# Qwiic_LED_Stick.net
KiCad netlist of a schematic drawn in EAGLE
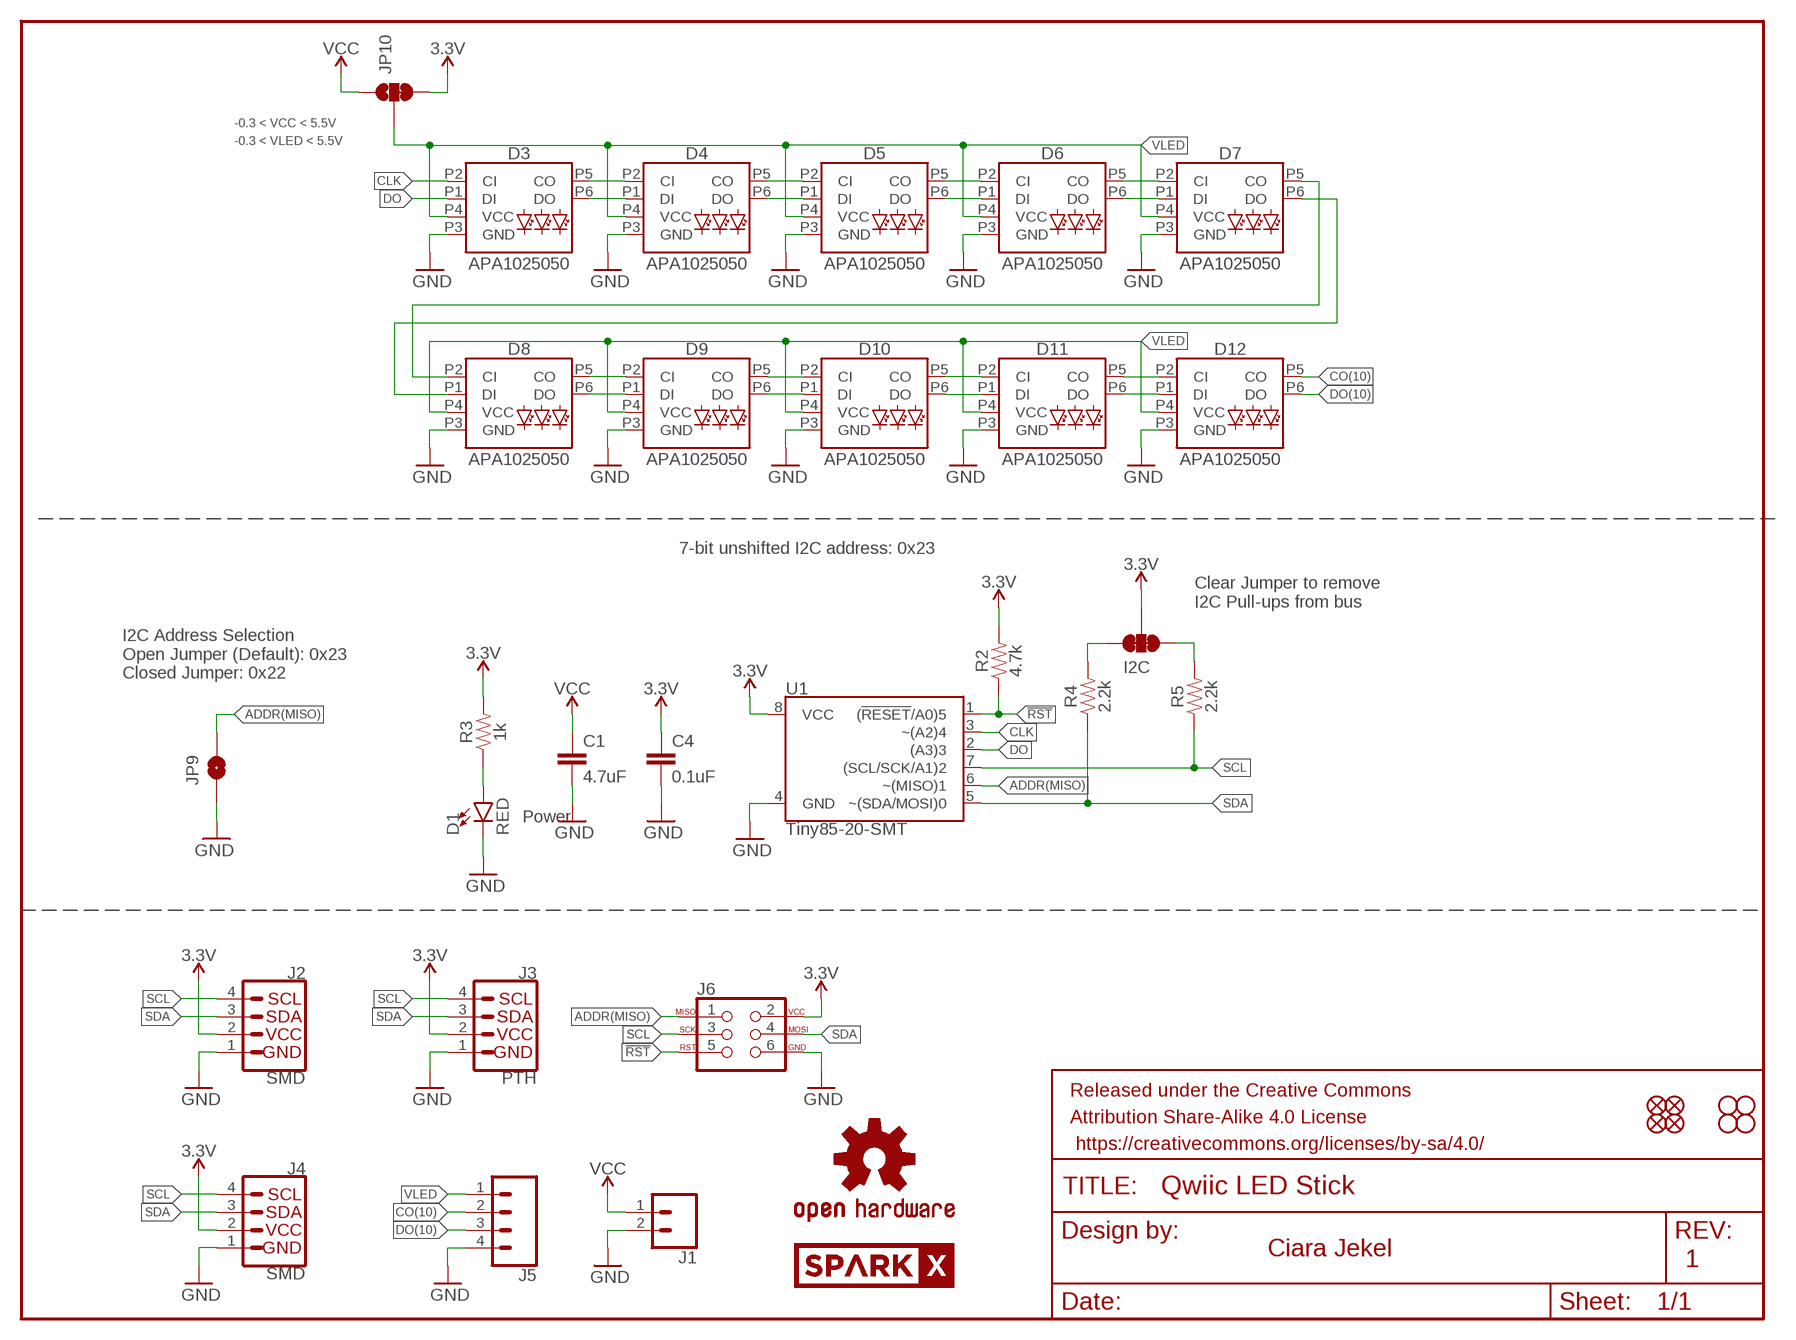
[diagram p0: schematic, sheet 1]

(export (version "E")
  (design (tool "Eeschema 10.0.6"))
  (components
    (comp (ref "C1")
      (value "4.7uF")
      (footprint "eagle-import:0603")
      (libsource (lib "eagle-import") (part "4.7UF-0603-6.3V-(10%)"))
    )
    (comp (ref "C4")
      (value "0.1uF")
      (footprint "eagle-import:0603")
      (libsource (lib "eagle-import") (part "0.1UF-0603-25V-(+80/-20%)"))
    )
    (comp (ref "D1")
      (value "RED")
      (footprint "eagle-import:LED-0603")
      (libsource (lib "eagle-import") (part "LED-RED0603"))
    )
    (comp (ref "D3")
      (value "APA1025050")
      (footprint "eagle-import:APA102-5050")
      (libsource (lib "eagle-import") (part "APA1025050"))
    )
    (comp (ref "D4")
      (value "APA1025050")
      (footprint "eagle-import:APA102-5050")
      (libsource (lib "eagle-import") (part "APA1025050"))
    )
    (comp (ref "D5")
      (value "APA1025050")
      (footprint "eagle-import:APA102-5050")
      (libsource (lib "eagle-import") (part "APA1025050"))
    )
    (comp (ref "D6")
      (value "APA1025050")
      (footprint "eagle-import:APA102-5050")
      (libsource (lib "eagle-import") (part "APA1025050"))
    )
    (comp (ref "D7")
      (value "APA1025050")
      (footprint "eagle-import:APA102-5050")
      (libsource (lib "eagle-import") (part "APA1025050"))
    )
    (comp (ref "D8")
      (value "APA1025050")
      (footprint "eagle-import:APA102-5050")
      (libsource (lib "eagle-import") (part "APA1025050"))
    )
    (comp (ref "D9")
      (value "APA1025050")
      (footprint "eagle-import:APA102-5050")
      (libsource (lib "eagle-import") (part "APA1025050"))
    )
    (comp (ref "D10")
      (value "APA1025050")
      (footprint "eagle-import:APA102-5050")
      (libsource (lib "eagle-import") (part "APA1025050"))
    )
    (comp (ref "D11")
      (value "APA1025050")
      (footprint "eagle-import:APA102-5050")
      (libsource (lib "eagle-import") (part "APA1025050"))
    )
    (comp (ref "D12")
      (value "APA1025050")
      (footprint "eagle-import:APA102-5050")
      (libsource (lib "eagle-import") (part "APA1025050"))
    )
    (comp (ref "FRAME1")
      (value "FRAME-LETTER")
      (footprint "eagle-import:CREATIVE_COMMONS")
      (libsource (lib "eagle-import") (part "FRAME-LETTER"))
    )
    (comp (ref "I2C")
      (value "JUMPER-SMT_3_2-NC_TRACE_SILK")
      (footprint "eagle-import:SMT-JUMPER_3_2-NC_TRACE_SILK")
      (libsource (lib "eagle-import") (part "JUMPER-SMT_3_2-NC_TRACE_SILK"))
    )
    (comp (ref "J1")
      (value "CONN_021X02_NO_SILK")
      (footprint "eagle-import:1X02_NO_SILK")
      (libsource (lib "eagle-import") (part "CONN_021X02_NO_SILK"))
    )
    (comp (ref "J2")
      (value "SMD")
      (footprint "eagle-import:1X04_1MM_RA")
      (libsource (lib "eagle-import") (part "I2C_STANDARDJS-1MM"))
    )
    (comp (ref "J3")
      (value "PTH")
      (footprint "eagle-import:1X04_NO_SILK")
      (libsource (lib "eagle-import") (part "I2C_STANDARD_NO_SILK"))
    )
    (comp (ref "J4")
      (value "SMD")
      (footprint "eagle-import:1X04_1MM_RA")
      (libsource (lib "eagle-import") (part "I2C_STANDARDJS-1MM"))
    )
    (comp (ref "J5")
      (value "CONN_041X04_NO_SILK")
      (footprint "eagle-import:1X04_NO_SILK")
      (libsource (lib "eagle-import") (part "CONN_041X04_NO_SILK"))
    )
    (comp (ref "J6")
      (value "AVR_SPI_PROG_3X2TESTPOINTS")
      (footprint "eagle-import:2X3_TEST_POINTS")
      (libsource (lib "eagle-import") (part "AVR_SPI_PROG_3X2TESTPOINTS"))
    )
    (comp (ref "JP1")
      (value "FIDUCIALUFIDUCIAL")
      (footprint "eagle-import:MICRO-FIDUCIAL")
      (libsource (lib "eagle-import") (part "FIDUCIALUFIDUCIAL"))
    )
    (comp (ref "JP2")
      (value "FIDUCIALUFIDUCIAL")
      (footprint "eagle-import:MICRO-FIDUCIAL")
      (libsource (lib "eagle-import") (part "FIDUCIALUFIDUCIAL"))
    )
    (comp (ref "JP3")
      (value "STAND-OFF")
      (footprint "eagle-import:STAND-OFF")
      (libsource (lib "eagle-import") (part "STAND-OFF"))
    )
    (comp (ref "JP4")
      (value "STAND-OFF")
      (footprint "eagle-import:STAND-OFF")
      (libsource (lib "eagle-import") (part "STAND-OFF"))
    )
    (comp (ref "JP5")
      (value "FIDUCIALUFIDUCIAL")
      (footprint "eagle-import:MICRO-FIDUCIAL")
      (libsource (lib "eagle-import") (part "FIDUCIALUFIDUCIAL"))
    )
    (comp (ref "JP6")
      (value "FIDUCIALUFIDUCIAL")
      (footprint "eagle-import:MICRO-FIDUCIAL")
      (libsource (lib "eagle-import") (part "FIDUCIALUFIDUCIAL"))
    )
    (comp (ref "JP7")
      (value "STAND-OFF")
      (footprint "eagle-import:STAND-OFF")
      (libsource (lib "eagle-import") (part "STAND-OFF"))
    )
    (comp (ref "JP8")
      (value "STAND-OFF")
      (footprint "eagle-import:STAND-OFF")
      (libsource (lib "eagle-import") (part "STAND-OFF"))
    )
    (comp (ref "JP9")
      (value "JUMPER-SMT_2_NO_SILK")
      (footprint "eagle-import:SMT-JUMPER_2_NO_SILK")
      (libsource (lib "eagle-import") (part "JUMPER-SMT_2_NO_SILK"))
    )
    (comp (ref "JP10")
      (value "JUMPER-SMT_3_1-NC_TRACE_SILK")
      (footprint "eagle-import:SMT-JUMPER_3_1-NC_TRACE_SILK")
      (libsource (lib "eagle-import") (part "JUMPER-SMT_3_1-NC_TRACE_SILK"))
    )
    (comp (ref "LOGO1")
      (value "OSHW-LOGOMINI")
      (footprint "eagle-import:OSHW-LOGO-MINI")
      (libsource (lib "eagle-import") (part "OSHW-LOGOMINI"))
    )
    (comp (ref "R2")
      (value "4.7k")
      (footprint "eagle-import:0603")
      (libsource (lib "eagle-import") (part "4.7KOHM-0603-1/10W-1%"))
    )
    (comp (ref "R3")
      (value "1k")
      (footprint "eagle-import:0603")
      (libsource (lib "eagle-import") (part "1KOHM-0603-1/10W-1%"))
    )
    (comp (ref "R4")
      (value "2.2k")
      (footprint "eagle-import:0603")
      (libsource (lib "eagle-import") (part "2.2KOHM-0603-1/10W-1%"))
    )
    (comp (ref "R5")
      (value "2.2k")
      (footprint "eagle-import:0603")
      (libsource (lib "eagle-import") (part "2.2KOHM-0603-1/10W-1%"))
    )
    (comp (ref "U$1")
      (value "SPARKX-LOGO4")
      (footprint "eagle-import:SPARKX-MEDIUM")
      (libsource (lib "eagle-import") (part "SPARKX-LOGO4"))
    )
    (comp (ref "U$2")
      (value "SPARKX-LOGO4")
      (footprint "eagle-import:SPARKX-MEDIUM")
      (libsource (lib "eagle-import") (part "SPARKX-LOGO4"))
    )
    (comp (ref "U1")
      (value "Tiny85-20-SMT")
      (footprint "eagle-import:SO08-EIAJ_MCU")
      (libsource (lib "eagle-import") (part "ATTINY85-ARDUINOTINY85-20-SMT"))
    )
  )
  (nets
    (net (code "1") (name "/~{RST}") (class "Default")
      (node (ref "J6") (pin "5") (pinfunction "5_5") (pintype "passive"))
      (node (ref "R2") (pin "1") (pinfunction "1_1") (pintype "passive"))
      (node (ref "U1") (pin "1") (pinfunction "(~{RESET}/A0)5_1") (pintype "bidirectional"))
    )
    (net (code "2") (name "3.3V") (class "Default")
      (node (ref "C4") (pin "1") (pinfunction "1_1") (pintype "passive"))
      (node (ref "I2C") (pin "2") (pinfunction "2_2") (pintype "passive"))
      (node (ref "J2") (pin "2") (pinfunction "VCC_2") (pintype "power_in"))
      (node (ref "J3") (pin "2") (pinfunction "VCC_2") (pintype "power_in"))
      (node (ref "J4") (pin "2") (pinfunction "VCC_2") (pintype "power_in"))
      (node (ref "J6") (pin "2") (pinfunction "2_2") (pintype "passive"))
      (node (ref "JP10") (pin "3") (pinfunction "3_3") (pintype "passive"))
      (node (ref "R2") (pin "2") (pinfunction "2_2") (pintype "passive"))
      (node (ref "R3") (pin "2") (pinfunction "2_2") (pintype "passive"))
      (node (ref "U1") (pin "8") (pinfunction "VCC_8") (pintype "bidirectional"))
    )
    (net (code "3") (name "ADDR(MISO)") (class "Default")
      (node (ref "J6") (pin "1") (pinfunction "1_1") (pintype "passive"))
      (node (ref "JP9") (pin "2") (pinfunction "2_2") (pintype "passive"))
      (node (ref "U1") (pin "6") (pinfunction "~{(MISO})1_6") (pintype "bidirectional"))
    )
    (net (code "4") (name "CLK") (class "Default")
      (node (ref "D3") (pin "P2") (pinfunction "CI_P2") (pintype "bidirectional"))
      (node (ref "U1") (pin "3") (pinfunction "~{(A2})4_3") (pintype "bidirectional"))
    )
    (net (code "5") (name "CO(10)") (class "Default")
      (node (ref "D12") (pin "P5") (pinfunction "CO_P5") (pintype "bidirectional"))
      (node (ref "J5") (pin "2") (pinfunction "2_2") (pintype "passive"))
    )
    (net (code "6") (name "DO") (class "Default")
      (node (ref "D3") (pin "P1") (pinfunction "DI_P1") (pintype "bidirectional"))
      (node (ref "U1") (pin "2") (pinfunction "(A3)3_2") (pintype "bidirectional"))
    )
    (net (code "7") (name "DO(10)") (class "Default")
      (node (ref "D12") (pin "P6") (pinfunction "DO_P6") (pintype "bidirectional"))
      (node (ref "J5") (pin "3") (pinfunction "3_3") (pintype "passive"))
    )
    (net (code "8") (name "GND") (class "Default")
      (node (ref "C1") (pin "2") (pinfunction "2_2") (pintype "passive"))
      (node (ref "C4") (pin "2") (pinfunction "2_2") (pintype "passive"))
      (node (ref "D1") (pin "C") (pinfunction "C_C") (pintype "passive"))
      (node (ref "D10") (pin "P3") (pinfunction "GND_P3") (pintype "bidirectional"))
      (node (ref "D11") (pin "P3") (pinfunction "GND_P3") (pintype "bidirectional"))
      (node (ref "D12") (pin "P3") (pinfunction "GND_P3") (pintype "bidirectional"))
      (node (ref "D3") (pin "P3") (pinfunction "GND_P3") (pintype "bidirectional"))
      (node (ref "D4") (pin "P3") (pinfunction "GND_P3") (pintype "bidirectional"))
      (node (ref "D5") (pin "P3") (pinfunction "GND_P3") (pintype "bidirectional"))
      (node (ref "D6") (pin "P3") (pinfunction "GND_P3") (pintype "bidirectional"))
      (node (ref "D7") (pin "P3") (pinfunction "GND_P3") (pintype "bidirectional"))
      (node (ref "D8") (pin "P3") (pinfunction "GND_P3") (pintype "bidirectional"))
      (node (ref "D9") (pin "P3") (pinfunction "GND_P3") (pintype "bidirectional"))
      (node (ref "J1") (pin "2") (pinfunction "2_2") (pintype "passive"))
      (node (ref "J2") (pin "1") (pinfunction "GND_1") (pintype "power_in"))
      (node (ref "J3") (pin "1") (pinfunction "GND_1") (pintype "power_in"))
      (node (ref "J4") (pin "1") (pinfunction "GND_1") (pintype "power_in"))
      (node (ref "J5") (pin "4") (pinfunction "4_4") (pintype "passive"))
      (node (ref "J6") (pin "6") (pinfunction "6_6") (pintype "passive"))
      (node (ref "JP9") (pin "1") (pinfunction "1_1") (pintype "passive"))
      (node (ref "U1") (pin "4") (pinfunction "GND_4") (pintype "bidirectional"))
    )
    (net (code "9") (name "Net-(D1-PadA)") (class "Default")
      (node (ref "D1") (pin "A") (pinfunction "A_A") (pintype "passive"))
      (node (ref "R3") (pin "1") (pinfunction "1_1") (pintype "passive"))
    )
    (net (code "10") (name "Net-(D3-CO)") (class "Default")
      (node (ref "D3") (pin "P5") (pinfunction "CO_P5") (pintype "bidirectional"))
      (node (ref "D4") (pin "P2") (pinfunction "CI_P2") (pintype "bidirectional"))
    )
    (net (code "11") (name "Net-(D3-DO)") (class "Default")
      (node (ref "D3") (pin "P6") (pinfunction "DO_P6") (pintype "bidirectional"))
      (node (ref "D4") (pin "P1") (pinfunction "DI_P1") (pintype "bidirectional"))
    )
    (net (code "12") (name "Net-(D4-CO)") (class "Default")
      (node (ref "D4") (pin "P5") (pinfunction "CO_P5") (pintype "bidirectional"))
      (node (ref "D5") (pin "P2") (pinfunction "CI_P2") (pintype "bidirectional"))
    )
    (net (code "13") (name "Net-(D4-DO)") (class "Default")
      (node (ref "D4") (pin "P6") (pinfunction "DO_P6") (pintype "bidirectional"))
      (node (ref "D5") (pin "P1") (pinfunction "DI_P1") (pintype "bidirectional"))
    )
    (net (code "14") (name "Net-(D5-CO)") (class "Default")
      (node (ref "D5") (pin "P5") (pinfunction "CO_P5") (pintype "bidirectional"))
      (node (ref "D6") (pin "P2") (pinfunction "CI_P2") (pintype "bidirectional"))
    )
    (net (code "15") (name "Net-(D5-DO)") (class "Default")
      (node (ref "D5") (pin "P6") (pinfunction "DO_P6") (pintype "bidirectional"))
      (node (ref "D6") (pin "P1") (pinfunction "DI_P1") (pintype "bidirectional"))
    )
    (net (code "16") (name "Net-(D6-CO)") (class "Default")
      (node (ref "D6") (pin "P5") (pinfunction "CO_P5") (pintype "bidirectional"))
      (node (ref "D7") (pin "P2") (pinfunction "CI_P2") (pintype "bidirectional"))
    )
    (net (code "17") (name "Net-(D6-DO)") (class "Default")
      (node (ref "D6") (pin "P6") (pinfunction "DO_P6") (pintype "bidirectional"))
      (node (ref "D7") (pin "P1") (pinfunction "DI_P1") (pintype "bidirectional"))
    )
    (net (code "18") (name "Net-(D7-CO)") (class "Default")
      (node (ref "D7") (pin "P5") (pinfunction "CO_P5") (pintype "bidirectional"))
      (node (ref "D8") (pin "P2") (pinfunction "CI_P2") (pintype "bidirectional"))
    )
    (net (code "19") (name "Net-(D7-DO)") (class "Default")
      (node (ref "D7") (pin "P6") (pinfunction "DO_P6") (pintype "bidirectional"))
      (node (ref "D8") (pin "P1") (pinfunction "DI_P1") (pintype "bidirectional"))
    )
    (net (code "20") (name "Net-(D8-CO)") (class "Default")
      (node (ref "D8") (pin "P5") (pinfunction "CO_P5") (pintype "bidirectional"))
      (node (ref "D9") (pin "P2") (pinfunction "CI_P2") (pintype "bidirectional"))
    )
    (net (code "21") (name "Net-(D8-DO)") (class "Default")
      (node (ref "D8") (pin "P6") (pinfunction "DO_P6") (pintype "bidirectional"))
      (node (ref "D9") (pin "P1") (pinfunction "DI_P1") (pintype "bidirectional"))
    )
    (net (code "22") (name "Net-(D10-CI)") (class "Default")
      (node (ref "D10") (pin "P2") (pinfunction "CI_P2") (pintype "bidirectional"))
      (node (ref "D9") (pin "P5") (pinfunction "CO_P5") (pintype "bidirectional"))
    )
    (net (code "23") (name "Net-(D10-CO)") (class "Default")
      (node (ref "D10") (pin "P5") (pinfunction "CO_P5") (pintype "bidirectional"))
      (node (ref "D11") (pin "P2") (pinfunction "CI_P2") (pintype "bidirectional"))
    )
    (net (code "24") (name "Net-(D10-DI)") (class "Default")
      (node (ref "D10") (pin "P1") (pinfunction "DI_P1") (pintype "bidirectional"))
      (node (ref "D9") (pin "P6") (pinfunction "DO_P6") (pintype "bidirectional"))
    )
    (net (code "25") (name "Net-(D10-DO)") (class "Default")
      (node (ref "D10") (pin "P6") (pinfunction "DO_P6") (pintype "bidirectional"))
      (node (ref "D11") (pin "P1") (pinfunction "DI_P1") (pintype "bidirectional"))
    )
    (net (code "26") (name "Net-(D11-CO)") (class "Default")
      (node (ref "D11") (pin "P5") (pinfunction "CO_P5") (pintype "bidirectional"))
      (node (ref "D12") (pin "P2") (pinfunction "CI_P2") (pintype "bidirectional"))
    )
    (net (code "27") (name "Net-(D11-DO)") (class "Default")
      (node (ref "D11") (pin "P6") (pinfunction "DO_P6") (pintype "bidirectional"))
      (node (ref "D12") (pin "P1") (pinfunction "DI_P1") (pintype "bidirectional"))
    )
    (net (code "28") (name "Net-(I2C-Pad1)") (class "Default")
      (node (ref "I2C") (pin "1") (pinfunction "1_1") (pintype "passive"))
      (node (ref "R5") (pin "2") (pinfunction "2_2") (pintype "passive"))
    )
    (net (code "29") (name "Net-(I2C-Pad3)") (class "Default")
      (node (ref "I2C") (pin "3") (pinfunction "3_3") (pintype "passive"))
      (node (ref "R4") (pin "2") (pinfunction "2_2") (pintype "passive"))
    )
    (net (code "30") (name "SCL") (class "Default")
      (node (ref "J2") (pin "4") (pinfunction "SCL_4") (pintype "passive"))
      (node (ref "J3") (pin "4") (pinfunction "SCL_4") (pintype "passive"))
      (node (ref "J4") (pin "4") (pinfunction "SCL_4") (pintype "passive"))
      (node (ref "J6") (pin "3") (pinfunction "3_3") (pintype "passive"))
      (node (ref "R5") (pin "1") (pinfunction "1_1") (pintype "passive"))
      (node (ref "U1") (pin "7") (pinfunction "(SCL/SCK/A1)2_7") (pintype "bidirectional"))
    )
    (net (code "31") (name "SDA") (class "Default")
      (node (ref "J2") (pin "3") (pinfunction "SDA_3") (pintype "passive"))
      (node (ref "J3") (pin "3") (pinfunction "SDA_3") (pintype "passive"))
      (node (ref "J4") (pin "3") (pinfunction "SDA_3") (pintype "passive"))
      (node (ref "J6") (pin "4") (pinfunction "4_4") (pintype "passive"))
      (node (ref "R4") (pin "1") (pinfunction "1_1") (pintype "passive"))
      (node (ref "U1") (pin "5") (pinfunction "~{(SDA/MOSI})0_5") (pintype "bidirectional"))
    )
    (net (code "32") (name "VCC") (class "Default")
      (node (ref "C1") (pin "1") (pinfunction "1_1") (pintype "passive"))
      (node (ref "J1") (pin "1") (pinfunction "1_1") (pintype "passive"))
      (node (ref "JP10") (pin "1") (pinfunction "1_1") (pintype "passive"))
    )
    (net (code "33") (name "VLED") (class "Default")
      (node (ref "D10") (pin "P4") (pinfunction "VCC_P4") (pintype "bidirectional"))
      (node (ref "D11") (pin "P4") (pinfunction "VCC_P4") (pintype "bidirectional"))
      (node (ref "D12") (pin "P4") (pinfunction "VCC_P4") (pintype "bidirectional"))
      (node (ref "D3") (pin "P4") (pinfunction "VCC_P4") (pintype "bidirectional"))
      (node (ref "D4") (pin "P4") (pinfunction "VCC_P4") (pintype "bidirectional"))
      (node (ref "D5") (pin "P4") (pinfunction "VCC_P4") (pintype "bidirectional"))
      (node (ref "D6") (pin "P4") (pinfunction "VCC_P4") (pintype "bidirectional"))
      (node (ref "D7") (pin "P4") (pinfunction "VCC_P4") (pintype "bidirectional"))
      (node (ref "D8") (pin "P4") (pinfunction "VCC_P4") (pintype "bidirectional"))
      (node (ref "D9") (pin "P4") (pinfunction "VCC_P4") (pintype "bidirectional"))
      (node (ref "J5") (pin "1") (pinfunction "1_1") (pintype "passive"))
      (node (ref "JP10") (pin "2") (pinfunction "2_2") (pintype "passive"))
    )
  )
)
